# 1_NZPP.net
KiCad netlist of a schematic drawn in Altium Designer
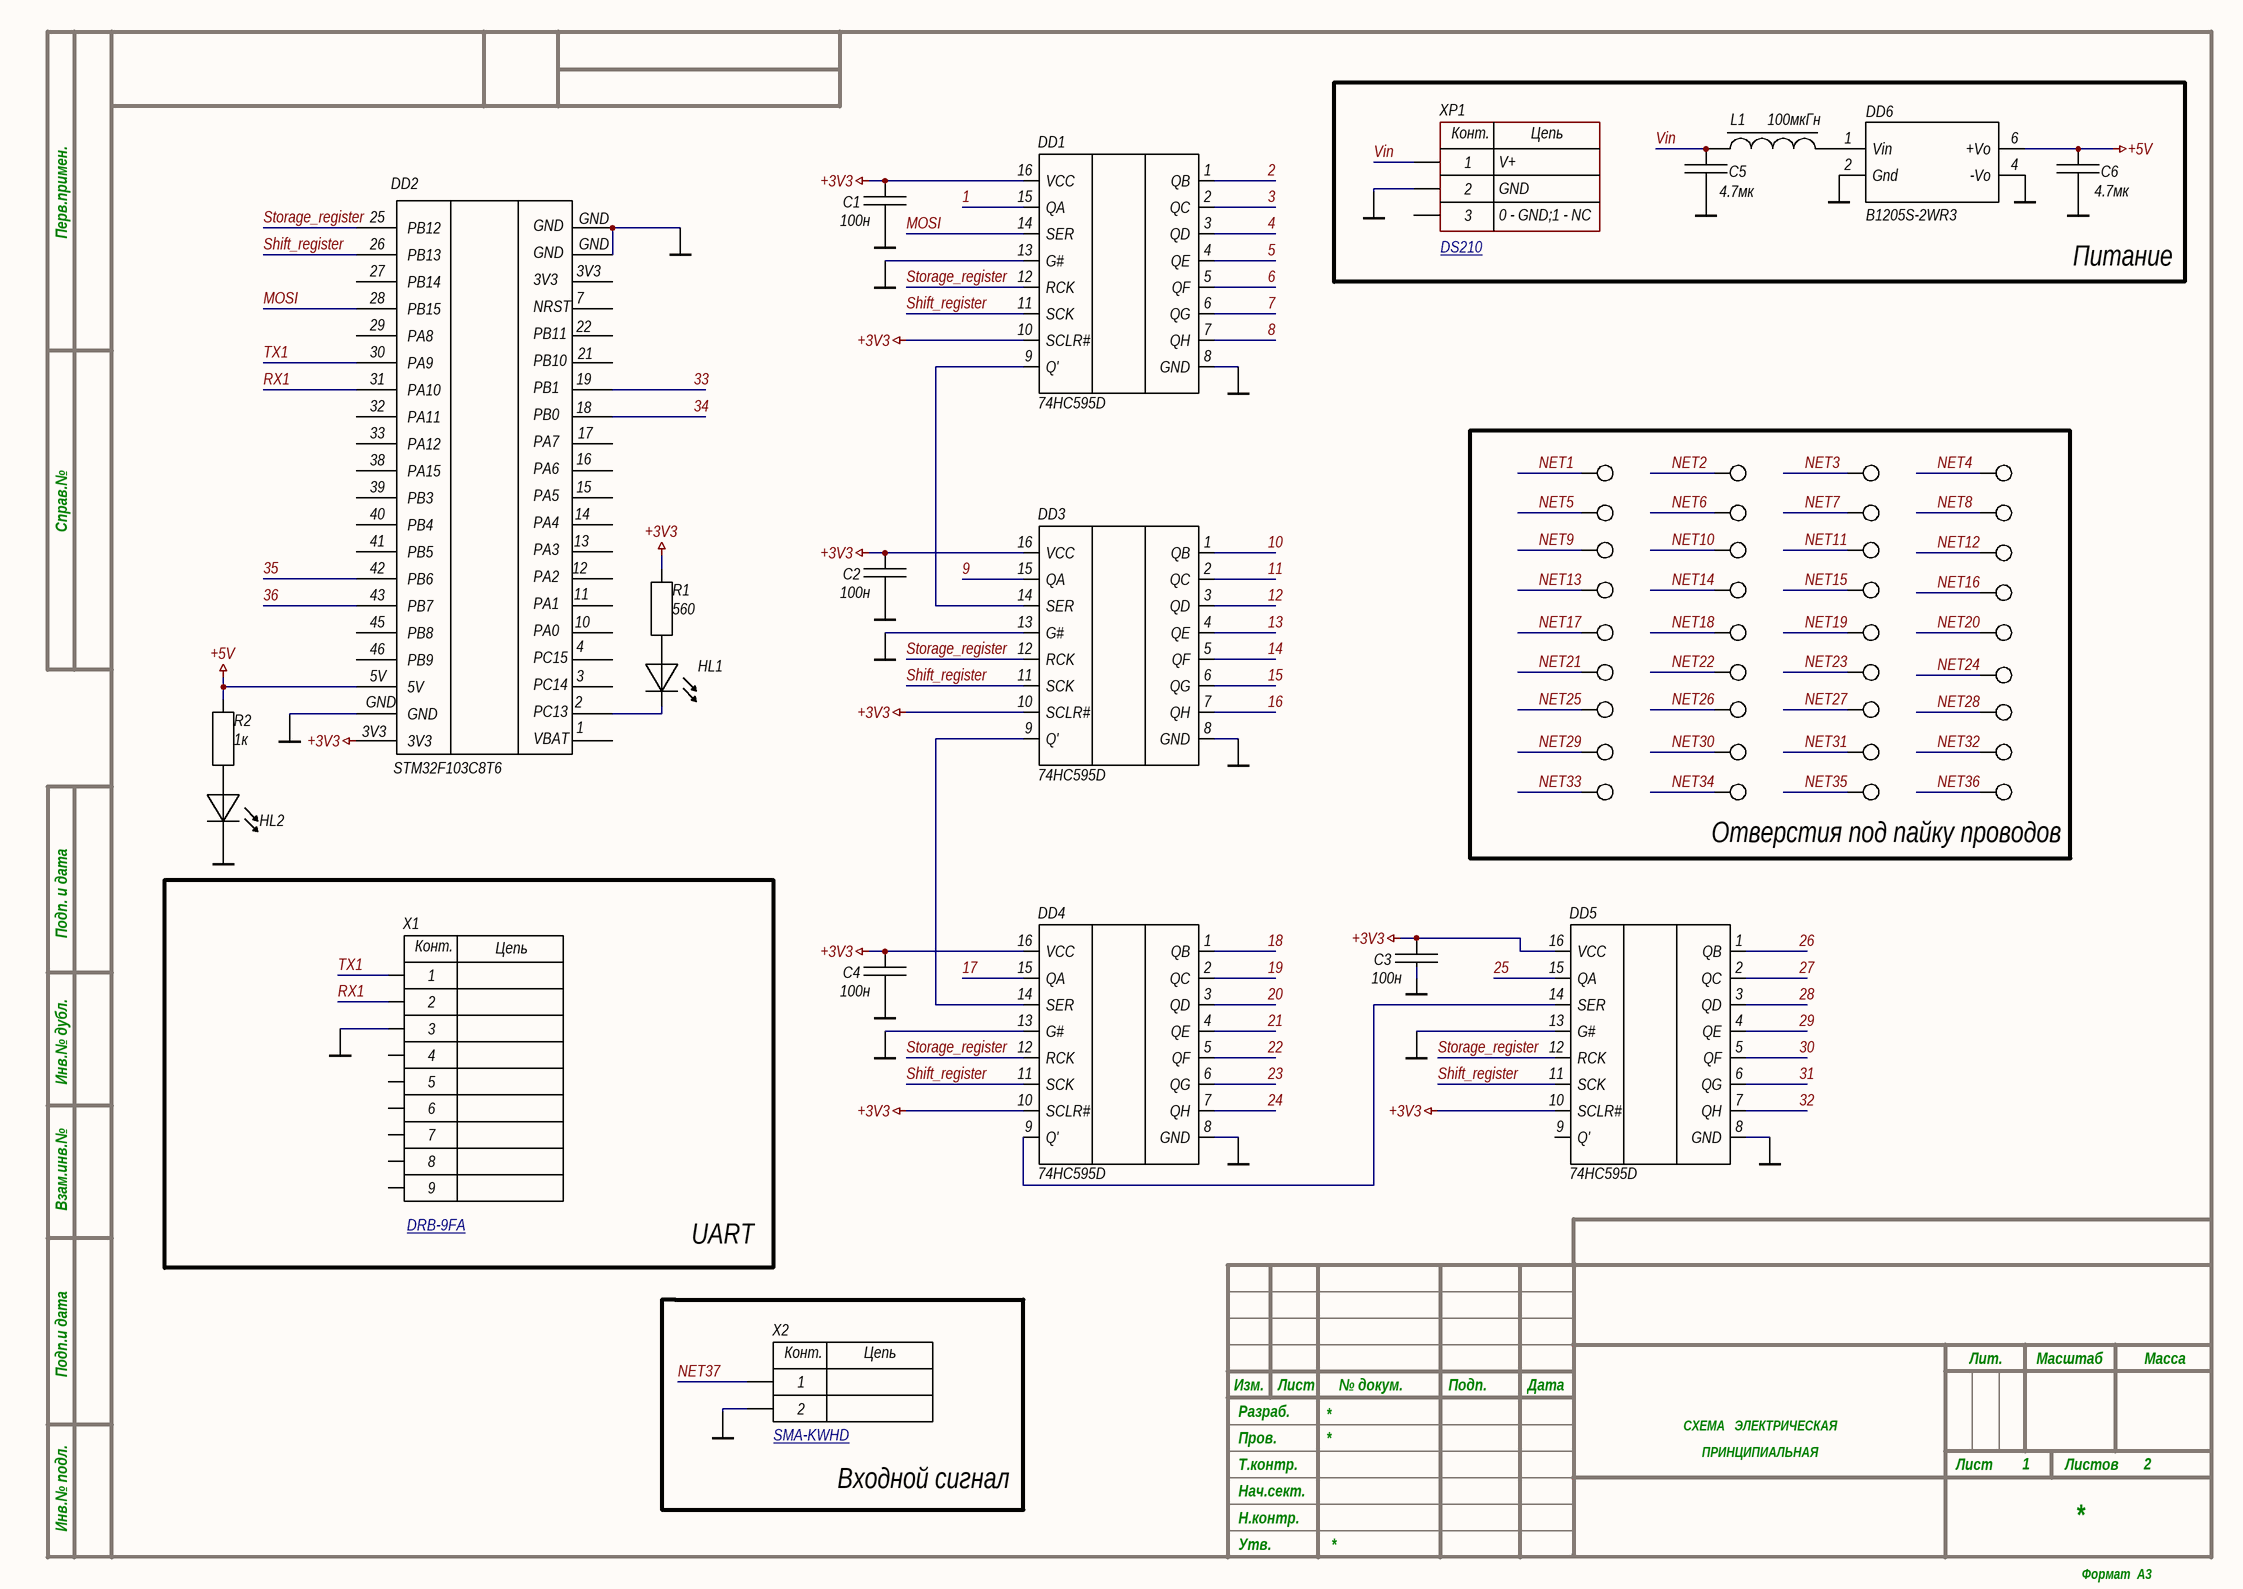
[diagram p0: 1.NZPP.SchDoc]

(export (version "E")
  (design (tool "Eeschema 10.0.6"))
  (components
    (comp (ref "*") (value "Point") (footprint "Point") (libsource (lib "Schlib1") (part "Point")))
    (comp (ref "*1") (value "Point") (footprint "Point") (libsource (lib "Schlib1") (part "Point")))
    (comp (ref "*2") (value "Point") (footprint "Point") (libsource (lib "Schlib1") (part "Point")))
    (comp (ref "*3") (value "Point") (footprint "Point") (libsource (lib "Schlib1") (part "Point")))
    (comp (ref "*4") (value "Point") (footprint "Point") (libsource (lib "Schlib1") (part "Point")))
    (comp (ref "*5") (value "Point") (footprint "Point") (libsource (lib "Schlib1") (part "Point")))
    (comp (ref "*6") (value "Point") (footprint "Point") (libsource (lib "Schlib1") (part "Point")))
    (comp (ref "*7") (value "Point") (footprint "Point") (libsource (lib "Schlib1") (part "Point")))
    (comp (ref "*8") (value "Point") (footprint "Point") (libsource (lib "Schlib1") (part "Point")))
    (comp (ref "*9") (value "Point") (footprint "Point") (libsource (lib "Schlib1") (part "Point")))
    (comp (ref "*10") (value "Point") (footprint "Point") (libsource (lib "Schlib1") (part "Point")))
    (comp (ref "*11") (value "Point") (footprint "Point") (libsource (lib "Schlib1") (part "Point")))
    (comp (ref "*12") (value "Point") (footprint "Point") (libsource (lib "Schlib1") (part "Point")))
    (comp (ref "*13") (value "Point") (footprint "Point") (libsource (lib "Schlib1") (part "Point")))
    (comp (ref "*14") (value "Point") (footprint "Point") (libsource (lib "Schlib1") (part "Point")))
    (comp (ref "*15") (value "Point") (footprint "Point") (libsource (lib "Schlib1") (part "Point")))
    (comp (ref "*16") (value "Point") (footprint "Point") (libsource (lib "Schlib1") (part "Point")))
    (comp (ref "*17") (value "Point") (footprint "Point") (libsource (lib "Schlib1") (part "Point")))
    (comp (ref "*18") (value "Point") (footprint "Point") (libsource (lib "Schlib1") (part "Point")))
    (comp (ref "*19") (value "Point") (footprint "Point") (libsource (lib "Schlib1") (part "Point")))
    (comp (ref "*20") (value "Point") (footprint "Point") (libsource (lib "Schlib1") (part "Point")))
    (comp (ref "*21") (value "Point") (footprint "Point") (libsource (lib "Schlib1") (part "Point")))
    (comp (ref "*22") (value "Point") (footprint "Point") (libsource (lib "Schlib1") (part "Point")))
    (comp (ref "*23") (value "Point") (footprint "Point") (libsource (lib "Schlib1") (part "Point")))
    (comp (ref "*24") (value "Point") (footprint "Point") (libsource (lib "Schlib1") (part "Point")))
    (comp (ref "*25") (value "Point") (footprint "Point") (libsource (lib "Schlib1") (part "Point")))
    (comp (ref "*26") (value "Point") (footprint "Point") (libsource (lib "Schlib1") (part "Point")))
    (comp (ref "*27") (value "Point") (footprint "Point") (libsource (lib "Schlib1") (part "Point")))
    (comp (ref "*28") (value "Point") (footprint "Point") (libsource (lib "Schlib1") (part "Point")))
    (comp (ref "*29") (value "Point") (footprint "Point") (libsource (lib "Schlib1") (part "Point")))
    (comp (ref "*30") (value "Point") (footprint "Point") (libsource (lib "Schlib1") (part "Point")))
    (comp (ref "*31") (value "Point") (footprint "Point") (libsource (lib "Schlib1") (part "Point")))
    (comp (ref "*32") (value "Point") (footprint "Point") (libsource (lib "Schlib1") (part "Point")))
    (comp (ref "*33") (value "Point") (footprint "Point") (libsource (lib "Schlib1") (part "Point")))
    (comp (ref "*34") (value "Point") (footprint "Point") (libsource (lib "Schlib1") (part "Point")))
    (comp (ref "*35") (value "Point") (footprint "Point") (libsource (lib "Schlib1") (part "Point")))
    (comp (ref "C1")
      (value "100н")
      (footprint "CAP: 0805")
      (libsource (lib "capacitor") (part "Ceramic_0805"))
    )
    (comp (ref "C2")
      (value "100н")
      (footprint "CAP: 0805")
      (libsource (lib "capacitor") (part "Ceramic_0805"))
    )
    (comp (ref "C3")
      (value "100н")
      (footprint "CAP: 0805")
      (libsource (lib "capacitor") (part "Ceramic_0805"))
    )
    (comp (ref "C4")
      (value "100н")
      (footprint "CAP: 0805")
      (libsource (lib "capacitor") (part "Ceramic_0805"))
    )
    (comp (ref "C5")
      (value "4.7мк")
      (footprint "CAP: 0805")
      (libsource (lib "capacitor") (part "Ceramic_0805"))
    )
    (comp (ref "C6")
      (value "4.7мк")
      (footprint "CAP: 0805")
      (libsource (lib "capacitor") (part "Ceramic_0805"))
    )
    (comp (ref "DD1") (value "74HC595D") (footprint "74HC595D") (libsource (lib "Schlib1") (part "74HC595D")))
    (comp (ref "DD2")
      (value "STM32F103C8T6")
      (footprint "STM32F103C8T6")
      (libsource (lib "Schlib1") (part "STM32F103"))
    )
    (comp (ref "DD3") (value "74HC595D") (footprint "74HC595D") (libsource (lib "") (part "74HC595D_1")))
    (comp (ref "DD4") (value "74HC595D") (footprint "74HC595D") (libsource (lib "") (part "74HC595D_1")))
    (comp (ref "DD5") (value "74HC595D") (footprint "74HC595D") (libsource (lib "") (part "74HC595D_1")))
    (comp (ref "DD6")
      (value "B1205S-2WR3")
      (footprint "B1205S-2WR3")
      (libsource (lib "Schlib1") (part "B1205S-2WR3"))
    )
    (comp (ref "HL1") (value "GNL-3012HD") (footprint "led green") (libsource (lib "Schlib1") (part "LED")))
    (comp (ref "HL2") (value "GNL-3012HD") (footprint "led") (libsource (lib "Schlib1") (part "LED")))
    (comp (ref "L1")
      (value "100мкГн")
      (footprint "100мкГн")
      (libsource (lib "Schlib1") (part "Дроссель 100мкГн CD43-101K"))
    )
    (comp (ref "R1")
      (value "560")
      (footprint "RES: 0805")
      (libsource (lib "resistor") (part "Resistor_0805"))
    )
    (comp (ref "R2") (value "1к") (footprint "RES: 0805") (libsource (lib "resistor") (part "Resistor_0805")))
    (comp (ref "X1") (value "DRB-9FA") (footprint "CON: DB-9F") (libsource (lib "Schlib1") (part "DRB-9FA")))
    (comp (ref "X2")
      (value "SMA-KWHD")
      (footprint "CON: SMA-KWHD")
      (libsource (lib "Schlib1") (part "Connector_terminal_2pin"))
    )
    (comp (ref "XP1") (value "DS210") (footprint "CON: DS210") (libsource (lib "Schlib1") (part "DS210")))
  )
  (nets
    (net (code "1") (name "+3V3") (class "Default")
      (node (ref "C1") (pin "2") (pinfunction "2_2") (pintype "passive"))
      (node (ref "C2") (pin "2") (pinfunction "2_2") (pintype "passive"))
      (node (ref "C3") (pin "2") (pinfunction "2_2") (pintype "passive"))
      (node (ref "C4") (pin "2") (pinfunction "2_2") (pintype "passive"))
      (node (ref "DD1") (pin "10") (pinfunction "SCLR#_10") (pintype "passive"))
      (node (ref "DD1") (pin "16") (pinfunction "VCC_16") (pintype "passive"))
      (node (ref "DD2") (pin "A2") (pinfunction "3V3_A2") (pintype "passive"))
      (node (ref "DD3") (pin "10") (pinfunction "SCLR#_10") (pintype "passive"))
      (node (ref "DD3") (pin "16") (pinfunction "VCC_16") (pintype "passive"))
      (node (ref "DD4") (pin "10") (pinfunction "SCLR#_10") (pintype "passive"))
      (node (ref "DD4") (pin "16") (pinfunction "VCC_16") (pintype "passive"))
      (node (ref "DD5") (pin "10") (pinfunction "SCLR#_10") (pintype "passive"))
      (node (ref "DD5") (pin "16") (pinfunction "VCC_16") (pintype "passive"))
      (node (ref "R1") (pin "2") (pinfunction "2_2") (pintype "passive"))
    )
    (net (code "2") (name "+5V") (class "Default")
      (node (ref "C6") (pin "2") (pinfunction "2_2") (pintype "passive"))
      (node (ref "DD2") (pin "5V") (pinfunction "5V_5V") (pintype "passive"))
      (node (ref "DD6") (pin "6") (pinfunction "+Vo_6") (pintype "passive"))
      (node (ref "R2") (pin "2") (pinfunction "2_2") (pintype "passive"))
    )
    (net (code "3") (name "/1") (class "Default")
      (node (ref "DD1") (pin "15") (pinfunction "QA_15") (pintype "passive"))
    )
    (net (code "4") (name "/2") (class "Default")
      (node (ref "DD1") (pin "1") (pinfunction "QB_1") (pintype "passive"))
    )
    (net (code "5") (name "/3") (class "Default")
      (node (ref "DD1") (pin "2") (pinfunction "QC_2") (pintype "passive"))
    )
    (net (code "6") (name "/4") (class "Default")
      (node (ref "DD1") (pin "3") (pinfunction "QD_3") (pintype "passive"))
    )
    (net (code "7") (name "/5") (class "Default")
      (node (ref "DD1") (pin "4") (pinfunction "QE_4") (pintype "passive"))
    )
    (net (code "8") (name "/6") (class "Default")
      (node (ref "DD1") (pin "5") (pinfunction "QF_5") (pintype "passive"))
    )
    (net (code "9") (name "/7") (class "Default")
      (node (ref "DD1") (pin "6") (pinfunction "QG_6") (pintype "passive"))
    )
    (net (code "10") (name "/8") (class "Default")
      (node (ref "DD1") (pin "7") (pinfunction "QH_7") (pintype "passive"))
    )
    (net (code "11") (name "/9") (class "Default")
      (node (ref "DD3") (pin "15") (pinfunction "QA_15") (pintype "passive"))
    )
    (net (code "12") (name "/10") (class "Default")
      (node (ref "DD3") (pin "1") (pinfunction "QB_1") (pintype "passive"))
    )
    (net (code "13") (name "/11") (class "Default")
      (node (ref "DD3") (pin "2") (pinfunction "QC_2") (pintype "passive"))
    )
    (net (code "14") (name "/12") (class "Default")
      (node (ref "DD3") (pin "3") (pinfunction "QD_3") (pintype "passive"))
    )
    (net (code "15") (name "/13") (class "Default")
      (node (ref "DD3") (pin "4") (pinfunction "QE_4") (pintype "passive"))
    )
    (net (code "16") (name "/14") (class "Default")
      (node (ref "DD3") (pin "5") (pinfunction "QF_5") (pintype "passive"))
    )
    (net (code "17") (name "/15") (class "Default")
      (node (ref "DD3") (pin "6") (pinfunction "QG_6") (pintype "passive"))
    )
    (net (code "18") (name "/16") (class "Default")
      (node (ref "DD3") (pin "7") (pinfunction "QH_7") (pintype "passive"))
    )
    (net (code "19") (name "/17") (class "Default")
      (node (ref "DD4") (pin "15") (pinfunction "QA_15") (pintype "passive"))
    )
    (net (code "20") (name "/18") (class "Default")
      (node (ref "DD4") (pin "1") (pinfunction "QB_1") (pintype "passive"))
    )
    (net (code "21") (name "/19") (class "Default")
      (node (ref "DD4") (pin "2") (pinfunction "QC_2") (pintype "passive"))
    )
    (net (code "22") (name "/20") (class "Default")
      (node (ref "DD4") (pin "3") (pinfunction "QD_3") (pintype "passive"))
    )
    (net (code "23") (name "/21") (class "Default")
      (node (ref "DD4") (pin "4") (pinfunction "QE_4") (pintype "passive"))
    )
    (net (code "24") (name "/22") (class "Default")
      (node (ref "DD4") (pin "5") (pinfunction "QF_5") (pintype "passive"))
    )
    (net (code "25") (name "/23") (class "Default")
      (node (ref "DD4") (pin "6") (pinfunction "QG_6") (pintype "passive"))
    )
    (net (code "26") (name "/24") (class "Default")
      (node (ref "DD4") (pin "7") (pinfunction "QH_7") (pintype "passive"))
    )
    (net (code "27") (name "/25") (class "Default")
      (node (ref "DD5") (pin "15") (pinfunction "QA_15") (pintype "passive"))
    )
    (net (code "28") (name "/26") (class "Default")
      (node (ref "DD5") (pin "1") (pinfunction "QB_1") (pintype "passive"))
    )
    (net (code "29") (name "/27") (class "Default")
      (node (ref "DD5") (pin "2") (pinfunction "QC_2") (pintype "passive"))
    )
    (net (code "30") (name "/28") (class "Default")
      (node (ref "DD5") (pin "3") (pinfunction "QD_3") (pintype "passive"))
    )
    (net (code "31") (name "/29") (class "Default")
      (node (ref "DD5") (pin "4") (pinfunction "QE_4") (pintype "passive"))
    )
    (net (code "32") (name "/30") (class "Default")
      (node (ref "DD5") (pin "5") (pinfunction "QF_5") (pintype "passive"))
    )
    (net (code "33") (name "/31") (class "Default")
      (node (ref "DD5") (pin "6") (pinfunction "QG_6") (pintype "passive"))
    )
    (net (code "34") (name "/32") (class "Default")
      (node (ref "DD5") (pin "7") (pinfunction "QH_7") (pintype "passive"))
    )
    (net (code "35") (name "/33") (class "Default")
      (node (ref "DD2") (pin "19") (pinfunction "PB1_19") (pintype "passive"))
    )
    (net (code "36") (name "/34") (class "Default")
      (node (ref "DD2") (pin "18") (pinfunction "PB0_18") (pintype "passive"))
    )
    (net (code "37") (name "/35") (class "Default")
      (node (ref "DD2") (pin "42") (pinfunction "PB6_42") (pintype "passive"))
    )
    (net (code "38") (name "/36") (class "Default")
      (node (ref "DD2") (pin "43") (pinfunction "PB7_43") (pintype "passive"))
    )
    (net (code "39") (name "/MOSI") (class "Default")
      (node (ref "DD1") (pin "14") (pinfunction "SER_14") (pintype "passive"))
      (node (ref "DD2") (pin "28") (pinfunction "PB15_28") (pintype "passive"))
    )
    (net (code "40") (name "/NET1") (class "Default")
      (node (ref "*") (pin "1") (pinfunction "4_1") (pintype "passive"))
    )
    (net (code "41") (name "/NET2") (class "Default")
      (node (ref "*1") (pin "1") (pinfunction "4_1") (pintype "passive"))
    )
    (net (code "42") (name "/NET3") (class "Default")
      (node (ref "*2") (pin "1") (pinfunction "4_1") (pintype "passive"))
    )
    (net (code "43") (name "/NET4") (class "Default")
      (node (ref "*3") (pin "1") (pinfunction "4_1") (pintype "passive"))
    )
    (net (code "44") (name "/NET5") (class "Default")
      (node (ref "*4") (pin "1") (pinfunction "4_1") (pintype "passive"))
    )
    (net (code "45") (name "/NET6") (class "Default")
      (node (ref "*5") (pin "1") (pinfunction "4_1") (pintype "passive"))
    )
    (net (code "46") (name "/NET7") (class "Default")
      (node (ref "*6") (pin "1") (pinfunction "4_1") (pintype "passive"))
    )
    (net (code "47") (name "/NET8") (class "Default")
      (node (ref "*7") (pin "1") (pinfunction "4_1") (pintype "passive"))
    )
    (net (code "48") (name "/NET9") (class "Default")
      (node (ref "*8") (pin "1") (pinfunction "4_1") (pintype "passive"))
    )
    (net (code "49") (name "/NET10") (class "Default")
      (node (ref "*9") (pin "1") (pinfunction "4_1") (pintype "passive"))
    )
    (net (code "50") (name "/NET11") (class "Default")
      (node (ref "*10") (pin "1") (pinfunction "4_1") (pintype "passive"))
    )
    (net (code "51") (name "/NET12") (class "Default")
      (node (ref "*11") (pin "1") (pinfunction "4_1") (pintype "passive"))
    )
    (net (code "52") (name "/NET13") (class "Default")
      (node (ref "*12") (pin "1") (pinfunction "4_1") (pintype "passive"))
    )
    (net (code "53") (name "/NET14") (class "Default")
      (node (ref "*13") (pin "1") (pinfunction "4_1") (pintype "passive"))
    )
    (net (code "54") (name "/NET15") (class "Default")
      (node (ref "*14") (pin "1") (pinfunction "4_1") (pintype "passive"))
    )
    (net (code "55") (name "/NET16") (class "Default")
      (node (ref "*15") (pin "1") (pinfunction "4_1") (pintype "passive"))
    )
    (net (code "56") (name "/NET17") (class "Default")
      (node (ref "*16") (pin "1") (pinfunction "4_1") (pintype "passive"))
    )
    (net (code "57") (name "/NET18") (class "Default")
      (node (ref "*17") (pin "1") (pinfunction "4_1") (pintype "passive"))
    )
    (net (code "58") (name "/NET19") (class "Default")
      (node (ref "*18") (pin "1") (pinfunction "4_1") (pintype "passive"))
    )
    (net (code "59") (name "/NET20") (class "Default")
      (node (ref "*19") (pin "1") (pinfunction "4_1") (pintype "passive"))
    )
    (net (code "60") (name "/NET21") (class "Default")
      (node (ref "*20") (pin "1") (pinfunction "4_1") (pintype "passive"))
    )
    (net (code "61") (name "/NET22") (class "Default")
      (node (ref "*21") (pin "1") (pinfunction "4_1") (pintype "passive"))
    )
    (net (code "62") (name "/NET23") (class "Default")
      (node (ref "*22") (pin "1") (pinfunction "4_1") (pintype "passive"))
    )
    (net (code "63") (name "/NET24") (class "Default")
      (node (ref "*23") (pin "1") (pinfunction "4_1") (pintype "passive"))
    )
    (net (code "64") (name "/NET25") (class "Default")
      (node (ref "*24") (pin "1") (pinfunction "4_1") (pintype "passive"))
    )
    (net (code "65") (name "/NET26") (class "Default")
      (node (ref "*25") (pin "1") (pinfunction "4_1") (pintype "passive"))
    )
    (net (code "66") (name "/NET27") (class "Default")
      (node (ref "*26") (pin "1") (pinfunction "4_1") (pintype "passive"))
    )
    (net (code "67") (name "/NET28") (class "Default")
      (node (ref "*27") (pin "1") (pinfunction "4_1") (pintype "passive"))
    )
    (net (code "68") (name "/NET29") (class "Default")
      (node (ref "*28") (pin "1") (pinfunction "4_1") (pintype "passive"))
    )
    (net (code "69") (name "/NET30") (class "Default")
      (node (ref "*29") (pin "1") (pinfunction "4_1") (pintype "passive"))
    )
    (net (code "70") (name "/NET31") (class "Default")
      (node (ref "*30") (pin "1") (pinfunction "4_1") (pintype "passive"))
    )
    (net (code "71") (name "/NET32") (class "Default")
      (node (ref "*31") (pin "1") (pinfunction "4_1") (pintype "passive"))
    )
    (net (code "72") (name "/NET33") (class "Default")
      (node (ref "*32") (pin "1") (pinfunction "4_1") (pintype "passive"))
    )
    (net (code "73") (name "/NET34") (class "Default")
      (node (ref "*33") (pin "1") (pinfunction "4_1") (pintype "passive"))
    )
    (net (code "74") (name "/NET35") (class "Default")
      (node (ref "*34") (pin "1") (pinfunction "4_1") (pintype "passive"))
    )
    (net (code "75") (name "/NET36") (class "Default")
      (node (ref "*35") (pin "1") (pinfunction "4_1") (pintype "passive"))
    )
    (net (code "76") (name "/NET37") (class "Default")
      (node (ref "X2") (pin "1") (pinfunction "1_1") (pintype "passive"))
    )
    (net (code "77") (name "/RX1") (class "Default")
      (node (ref "DD2") (pin "31") (pinfunction "PA10_31") (pintype "passive"))
      (node (ref "X1") (pin "2") (pinfunction "2_2") (pintype "passive"))
    )
    (net (code "78") (name "/Shift_register") (class "Default")
      (node (ref "DD1") (pin "11") (pinfunction "SCK_11") (pintype "passive"))
      (node (ref "DD2") (pin "26") (pinfunction "PB13_26") (pintype "passive"))
      (node (ref "DD3") (pin "11") (pinfunction "SCK_11") (pintype "passive"))
      (node (ref "DD4") (pin "11") (pinfunction "SCK_11") (pintype "passive"))
      (node (ref "DD5") (pin "11") (pinfunction "SCK_11") (pintype "passive"))
    )
    (net (code "79") (name "/Storage_register") (class "Default")
      (node (ref "DD1") (pin "12") (pinfunction "RCK_12") (pintype "passive"))
      (node (ref "DD2") (pin "25") (pinfunction "PB12_25") (pintype "passive"))
      (node (ref "DD3") (pin "12") (pinfunction "RCK_12") (pintype "passive"))
      (node (ref "DD4") (pin "12") (pinfunction "RCK_12") (pintype "passive"))
      (node (ref "DD5") (pin "12") (pinfunction "RCK_12") (pintype "passive"))
    )
    (net (code "80") (name "/TX1") (class "Default")
      (node (ref "DD2") (pin "30") (pinfunction "PA9_30") (pintype "passive"))
      (node (ref "X1") (pin "1") (pinfunction "1_1") (pintype "passive"))
    )
    (net (code "81") (name "/Vin") (class "Default")
      (node (ref "C5") (pin "2") (pinfunction "2_2") (pintype "passive"))
      (node (ref "L1") (pin "1") (pinfunction "1_1") (pintype "passive"))
      (node (ref "XP1") (pin "1") (pinfunction "1_1") (pintype "passive"))
    )
    (net (code "82") (name "GND") (class "Default")
      (node (ref "C1") (pin "1") (pinfunction "1_1") (pintype "passive"))
      (node (ref "C2") (pin "1") (pinfunction "1_1") (pintype "passive"))
      (node (ref "C3") (pin "1") (pinfunction "1_1") (pintype "passive"))
      (node (ref "C4") (pin "1") (pinfunction "1_1") (pintype "passive"))
      (node (ref "C5") (pin "1") (pinfunction "1_1") (pintype "passive"))
      (node (ref "C6") (pin "1") (pinfunction "1_1") (pintype "passive"))
      (node (ref "DD1") (pin "13") (pinfunction "G#_13") (pintype "passive"))
      (node (ref "DD1") (pin "8") (pinfunction "GND_8") (pintype "passive"))
      (node (ref "DD2") (pin "GND") (pinfunction "GND_GND") (pintype "passive"))
      (node (ref "DD3") (pin "13") (pinfunction "G#_13") (pintype "passive"))
      (node (ref "DD3") (pin "8") (pinfunction "GND_8") (pintype "passive"))
      (node (ref "DD4") (pin "13") (pinfunction "G#_13") (pintype "passive"))
      (node (ref "DD4") (pin "8") (pinfunction "GND_8") (pintype "passive"))
      (node (ref "DD5") (pin "13") (pinfunction "G#_13") (pintype "passive"))
      (node (ref "DD5") (pin "8") (pinfunction "GND_8") (pintype "passive"))
      (node (ref "DD6") (pin "2") (pinfunction "Gnd_2") (pintype "passive"))
      (node (ref "DD6") (pin "4") (pinfunction "-Vo_4") (pintype "passive"))
      (node (ref "HL2") (pin "2") (pinfunction "C_2") (pintype "passive"))
      (node (ref "X1") (pin "3") (pinfunction "3_3") (pintype "power_in"))
      (node (ref "X2") (pin "2") (pinfunction "2_2") (pintype "passive"))
      (node (ref "XP1") (pin "2") (pinfunction "2_2") (pintype "passive"))
    )
    (net (code "83") (name "Net-(DD1-Q')") (class "Default")
      (node (ref "DD1") (pin "9") (pinfunction "Q'_9") (pintype "passive"))
      (node (ref "DD3") (pin "14") (pinfunction "SER_14") (pintype "passive"))
    )
    (net (code "84") (name "Net-(DD2-PC13)") (class "Default")
      (node (ref "DD2") (pin "2") (pinfunction "PC13_2") (pintype "passive"))
      (node (ref "HL1") (pin "2") (pinfunction "C_2") (pintype "passive"))
    )
    (net (code "85") (name "Net-(DD3-Q')") (class "Default")
      (node (ref "DD3") (pin "9") (pinfunction "Q'_9") (pintype "passive"))
      (node (ref "DD4") (pin "14") (pinfunction "SER_14") (pintype "passive"))
    )
    (net (code "86") (name "Net-(DD4-Q')") (class "Default")
      (node (ref "DD4") (pin "9") (pinfunction "Q'_9") (pintype "passive"))
      (node (ref "DD5") (pin "14") (pinfunction "SER_14") (pintype "passive"))
    )
    (net (code "87") (name "Net-(DD6-Vin)") (class "Default")
      (node (ref "DD6") (pin "1") (pinfunction "Vin_1") (pintype "passive"))
      (node (ref "L1") (pin "2") (pinfunction "2_2") (pintype "passive"))
    )
    (net (code "88") (name "Net-(HL1-A)") (class "Default")
      (node (ref "HL1") (pin "1") (pinfunction "A_1") (pintype "passive"))
      (node (ref "R1") (pin "1") (pinfunction "1_1") (pintype "passive"))
    )
    (net (code "89") (name "Net-(HL2-A)") (class "Default")
      (node (ref "HL2") (pin "1") (pinfunction "A_1") (pintype "passive"))
      (node (ref "R2") (pin "1") (pinfunction "1_1") (pintype "passive"))
    )
    (net (code "90") (name "unconnected-(DD2-3V3-PadA1)") (class "Default")
      (node (ref "DD2") (pin "A1") (pinfunction "3V3_A1") (pintype "passive"))
    )
    (net (code "91") (name "unconnected-(DD2-NRST-Pad7)") (class "Default")
      (node (ref "DD2") (pin "7") (pinfunction "NRST_7") (pintype "passive"))
    )
    (net (code "92") (name "unconnected-(DD2-PA0-Pad10)") (class "Default")
      (node (ref "DD2") (pin "10") (pinfunction "PA0_10") (pintype "passive"))
    )
    (net (code "93") (name "unconnected-(DD2-PA1-Pad11)") (class "Default")
      (node (ref "DD2") (pin "11") (pinfunction "PA1_11") (pintype "passive"))
    )
    (net (code "94") (name "unconnected-(DD2-PA2-Pad12)") (class "Default")
      (node (ref "DD2") (pin "12") (pinfunction "PA2_12") (pintype "passive"))
    )
    (net (code "95") (name "unconnected-(DD2-PA3-Pad13)") (class "Default")
      (node (ref "DD2") (pin "13") (pinfunction "PA3_13") (pintype "passive"))
    )
    (net (code "96") (name "unconnected-(DD2-PA4-Pad14)") (class "Default")
      (node (ref "DD2") (pin "14") (pinfunction "PA4_14") (pintype "passive"))
    )
    (net (code "97") (name "unconnected-(DD2-PA5-Pad15)") (class "Default")
      (node (ref "DD2") (pin "15") (pinfunction "PA5_15") (pintype "passive"))
    )
    (net (code "98") (name "unconnected-(DD2-PA6-Pad16)") (class "Default")
      (node (ref "DD2") (pin "16") (pinfunction "PA6_16") (pintype "passive"))
    )
    (net (code "99") (name "unconnected-(DD2-PA7-Pad17)") (class "Default")
      (node (ref "DD2") (pin "17") (pinfunction "PA7_17") (pintype "passive"))
    )
    (net (code "100") (name "unconnected-(DD2-PA8-Pad29)") (class "Default")
      (node (ref "DD2") (pin "29") (pinfunction "PA8_29") (pintype "passive"))
    )
    (net (code "101") (name "unconnected-(DD2-PA11-Pad32)") (class "Default")
      (node (ref "DD2") (pin "32") (pinfunction "PA11_32") (pintype "passive"))
    )
    (net (code "102") (name "unconnected-(DD2-PA12-Pad33)") (class "Default")
      (node (ref "DD2") (pin "33") (pinfunction "PA12_33") (pintype "passive"))
    )
    (net (code "103") (name "unconnected-(DD2-PA15-Pad38)") (class "Default")
      (node (ref "DD2") (pin "38") (pinfunction "PA15_38") (pintype "passive"))
    )
    (net (code "104") (name "unconnected-(DD2-PB3-Pad39)") (class "Default")
      (node (ref "DD2") (pin "39") (pinfunction "PB3_39") (pintype "passive"))
    )
    (net (code "105") (name "unconnected-(DD2-PB4-Pad40)") (class "Default")
      (node (ref "DD2") (pin "40") (pinfunction "PB4_40") (pintype "passive"))
    )
    (net (code "106") (name "unconnected-(DD2-PB5-Pad41)") (class "Default")
      (node (ref "DD2") (pin "41") (pinfunction "PB5_41") (pintype "passive"))
    )
    (net (code "107") (name "unconnected-(DD2-PB8-Pad45)") (class "Default")
      (node (ref "DD2") (pin "45") (pinfunction "PB8_45") (pintype "passive"))
    )
    (net (code "108") (name "unconnected-(DD2-PB9-Pad46)") (class "Default")
      (node (ref "DD2") (pin "46") (pinfunction "PB9_46") (pintype "passive"))
    )
    (net (code "109") (name "unconnected-(DD2-PB10-Pad21)") (class "Default")
      (node (ref "DD2") (pin "21") (pinfunction "PB10_21") (pintype "passive"))
    )
    (net (code "110") (name "unconnected-(DD2-PB11-Pad22)") (class "Default")
      (node (ref "DD2") (pin "22") (pinfunction "PB11_22") (pintype "passive"))
    )
    (net (code "111") (name "unconnected-(DD2-PB14-Pad27)") (class "Default")
      (node (ref "DD2") (pin "27") (pinfunction "PB14_27") (pintype "passive"))
    )
    (net (code "112") (name "unconnected-(DD2-PC14-Pad3)") (class "Default")
      (node (ref "DD2") (pin "3") (pinfunction "PC14_3") (pintype "passive"))
    )
    (net (code "113") (name "unconnected-(DD2-PC15-Pad4)") (class "Default")
      (node (ref "DD2") (pin "4") (pinfunction "PC15_4") (pintype "passive"))
    )
    (net (code "114") (name "unconnected-(DD2-Vbat-Pad1)") (class "Default")
      (node (ref "DD2") (pin "1") (pinfunction "Vbat_1") (pintype "passive"))
    )
    (net (code "115") (name "unconnected-(DD5-Q'-Pad9)") (class "Default")
      (node (ref "DD5") (pin "9") (pinfunction "Q'_9") (pintype "passive"))
    )
    (net (code "116") (name "unconnected-(X1-Pad4)") (class "Default")
      (node (ref "X1") (pin "4") (pinfunction "4_4") (pintype "power_in"))
    )
    (net (code "117") (name "unconnected-(X1-Pad5)") (class "Default")
      (node (ref "X1") (pin "5") (pinfunction "5_5") (pintype "power_in"))
    )
    (net (code "118") (name "unconnected-(X1-Pad6)") (class "Default")
      (node (ref "X1") (pin "6") (pinfunction "6_6") (pintype "power_in"))
    )
    (net (code "119") (name "unconnected-(X1-Pad7)") (class "Default")
      (node (ref "X1") (pin "7") (pinfunction "7_7") (pintype "power_in"))
    )
    (net (code "120") (name "unconnected-(X1-Pad8)") (class "Default")
      (node (ref "X1") (pin "8") (pinfunction "8_8") (pintype "power_in"))
    )
    (net (code "121") (name "unconnected-(X1-Pad9)") (class "Default")
      (node (ref "X1") (pin "9") (pinfunction "9_9") (pintype "power_in"))
    )
    (net (code "122") (name "unconnected-(XP1-Pad3)") (class "Default")
      (node (ref "XP1") (pin "3") (pinfunction "3_3") (pintype "passive"))
    )
  )
)
